# STM8_DevBoard.net
KiCad netlist of a schematic drawn in Altium Designer
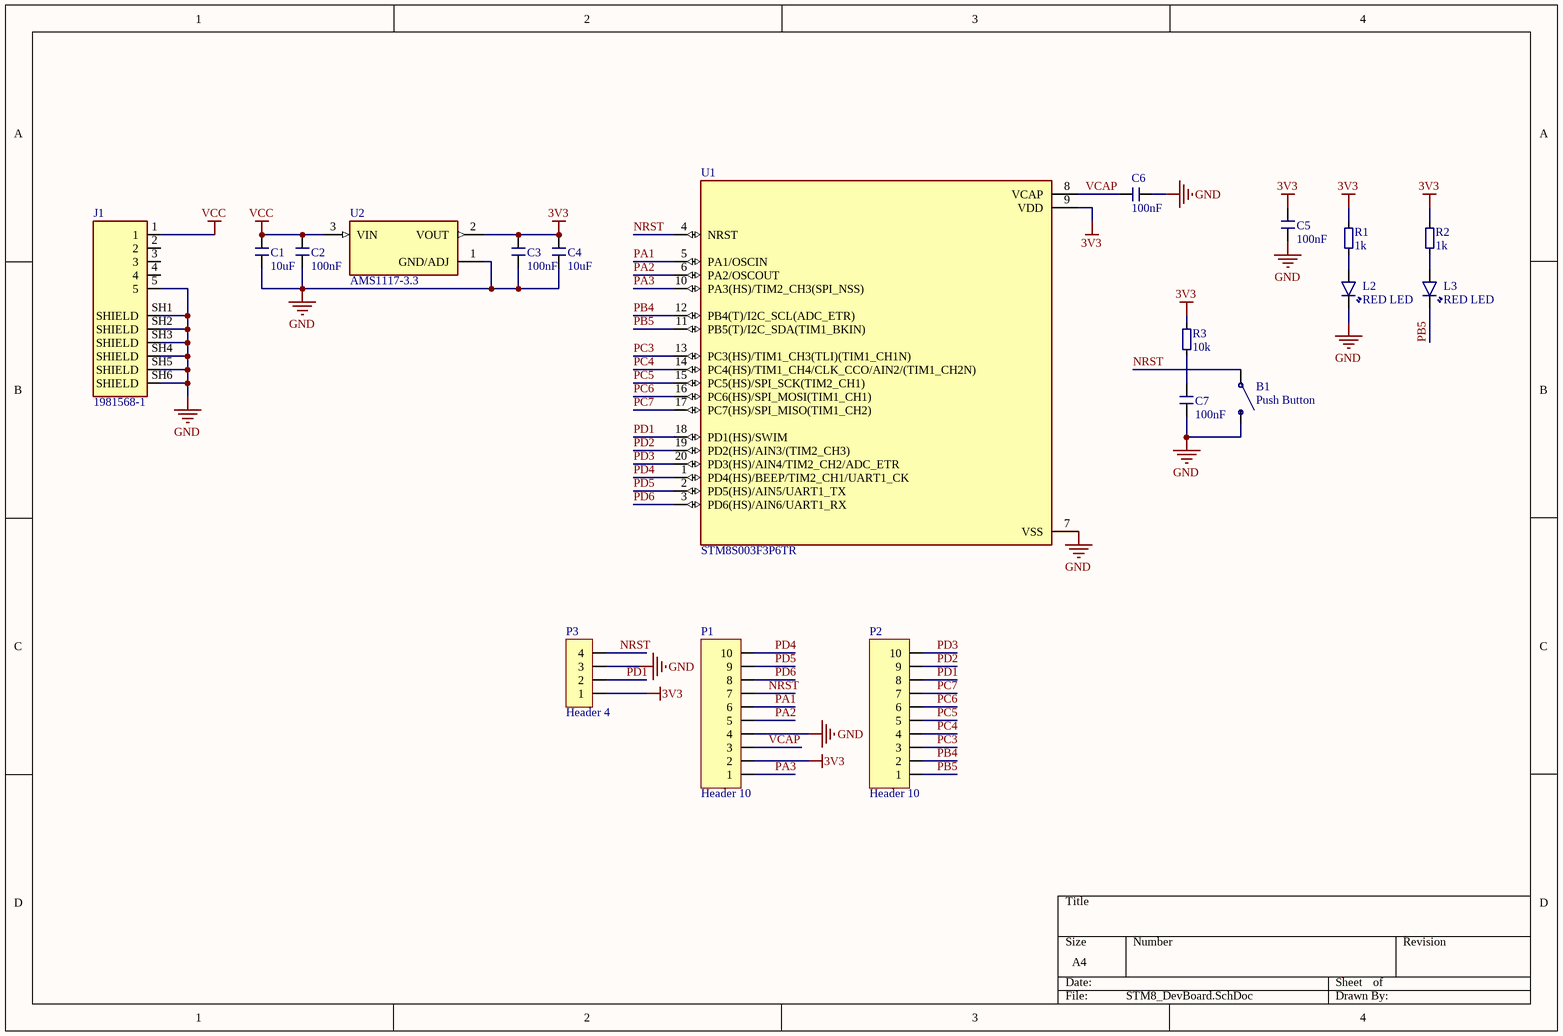
[diagram p0: STM8_DevBoard.SchDoc]

(export (version "E")
  (design (tool "Eeschema 10.0.6"))
  (components
    (comp (ref "B1")
      (value "Push Button")
      (footprint "NRST")
      (libsource (lib "STM8_DevBoard") (part "Push Button"))
    )
    (comp (ref "C1")
      (value "10uF")
      (footprint "1206_Capacitor")
      (libsource (lib "STM8_DevBoard") (part "1206_Capacitor"))
    )
    (comp (ref "C2")
      (value "100nF")
      (footprint "1206_Capacitor")
      (libsource (lib "STM8_DevBoard") (part "1206_Capacitor"))
    )
    (comp (ref "C3")
      (value "100nF")
      (footprint "1206_Capacitor")
      (libsource (lib "STM8_DevBoard") (part "1206_Capacitor"))
    )
    (comp (ref "C4")
      (value "10uF")
      (footprint "1206_Capacitor")
      (libsource (lib "STM8_DevBoard") (part "1206_Capacitor"))
    )
    (comp (ref "C5")
      (value "100nF")
      (footprint "1206_Capacitor")
      (libsource (lib "STM8_DevBoard") (part "1206_Capacitor"))
    )
    (comp (ref "C6")
      (value "100nF")
      (footprint "1206_Capacitor")
      (libsource (lib "STM8_DevBoard") (part "1206_Capacitor"))
    )
    (comp (ref "C7")
      (value "100nF")
      (footprint "1206_Capacitor")
      (libsource (lib "STM8_DevBoard") (part "1206_Capacitor"))
    )
    (comp (ref "J1")
      (value "1981568-1")
      (footprint "TE_1981568-1")
      (libsource (lib "1981568-1") (part "1981568-1"))
    )
    (comp (ref "L2")
      (value "RED LED")
      (footprint "0805_LED")
      (libsource (lib "STM8_DevBoard") (part "0805_LED"))
    )
    (comp (ref "L3")
      (value "RED LED")
      (footprint "0805_LED")
      (libsource (lib "STM8_DevBoard") (part "0805_LED"))
    )
    (comp (ref "P1")
      (value "Header 10")
      (footprint "Header 10")
      (libsource (lib "STM8_DevBoard") (part "Header 10"))
    )
    (comp (ref "P2")
      (value "Header 10")
      (footprint "Header 10")
      (libsource (lib "STM8_DevBoard") (part "Header 10"))
    )
    (comp (ref "P3")
      (value "Header 4")
      (footprint "Header 4")
      (libsource (lib "STM8_DevBoard") (part "Header 4"))
    )
    (comp (ref "R1")
      (value "1k")
      (footprint "1206 Resistor")
      (libsource (lib "STM8_DevBoard") (part "1206 Resistor"))
    )
    (comp (ref "R2")
      (value "1k")
      (footprint "1206 Resistor")
      (libsource (lib "STM8_DevBoard") (part "1206 Resistor"))
    )
    (comp (ref "R3")
      (value "10k")
      (footprint "1206 Resistor")
      (libsource (lib "STM8_DevBoard") (part "1206 Resistor"))
    )
    (comp (ref "U1")
      (value "STM8S003F3P6TR")
      (footprint "SOP65P640X120-20N")
      (description "STM8 STM8S Microcontroller IC 8-Bit 16MHz 8KB (8K x 8) FLASH 20-TSSOP")
      (fields (field (name "MF") "STMicroelectronics"))
      (libsource (lib "STM8S003F3P6TR") (part "STM8S003F3P6TR"))
    )
    (comp (ref "U2")
      (value "AMS1117-3.3")
      (footprint "SOT229P700X180-4N")
      (description "Sot223/Pkg 1-Amp 3.3-Volt Low Drop Out Voltage Regulatator")
      (fields (field (name "MF") "Advanced Monolithic Systems"))
      (libsource (lib "AMS1117-3.3") (part "AMS1117-3.3"))
    )
  )
  (nets
    (net (code "1") (name "/NRST") (class "Default")
      (node (ref "B1") (pin "1") (pinfunction "1_1") (pintype "passive"))
      (node (ref "P1") (pin "7") (pinfunction "7_7") (pintype "passive"))
      (node (ref "P3") (pin "4") (pinfunction "4_4") (pintype "passive"))
      (node (ref "U1") (pin "4") (pinfunction "NRST_4") (pintype "bidirectional"))
    )
    (net (code "2") (name "/PA1") (class "Default")
      (node (ref "P1") (pin "6") (pinfunction "6_6") (pintype "passive"))
      (node (ref "U1") (pin "5") (pinfunction "PA1/OSCIN_5") (pintype "bidirectional"))
    )
    (net (code "3") (name "/PA2") (class "Default")
      (node (ref "P1") (pin "5") (pinfunction "5_5") (pintype "passive"))
      (node (ref "U1") (pin "6") (pinfunction "PA2/OSCOUT_6") (pintype "bidirectional"))
    )
    (net (code "4") (name "/PA3") (class "Default")
      (node (ref "P1") (pin "1") (pinfunction "1_1") (pintype "passive"))
      (node (ref "U1") (pin "10") (pinfunction "PA3(HS)/TIM2_CH3(SPI_NSS)_10") (pintype "bidirectional"))
    )
    (net (code "5") (name "/PB4") (class "Default")
      (node (ref "P2") (pin "2") (pinfunction "2_2") (pintype "passive"))
      (node (ref "U1") (pin "12") (pinfunction "PB4(T)/I2C_SCL(ADC_ETR)_12") (pintype "bidirectional"))
    )
    (net (code "6") (name "/PB5") (class "Default")
      (node (ref "L3") (pin "L_2") (pinfunction "L_2_L_2") (pintype "passive"))
      (node (ref "P2") (pin "1") (pinfunction "1_1") (pintype "passive"))
      (node (ref "U1") (pin "11") (pinfunction "PB5(T)/I2C_SDA(TIM1_BKIN)_11") (pintype "bidirectional"))
    )
    (net (code "7") (name "/PC3") (class "Default")
      (node (ref "P2") (pin "3") (pinfunction "3_3") (pintype "passive"))
      (node (ref "U1") (pin "13") (pinfunction "PC3(HS)/TIM1_CH3(TLI)(TIM1_CH1N)_13") (pintype "bidirectional"))
    )
    (net (code "8") (name "/PC4") (class "Default")
      (node (ref "P2") (pin "4") (pinfunction "4_4") (pintype "passive"))
      (node (ref "U1") (pin "14") (pinfunction "PC4(HS)/TIM1_CH4/CLK_CCO/AIN2/(TIM1_CH2N)_14") (pintype "bidirectional"))
    )
    (net (code "9") (name "/PC5") (class "Default")
      (node (ref "P2") (pin "5") (pinfunction "5_5") (pintype "passive"))
      (node (ref "U1") (pin "15") (pinfunction "PC5(HS)/SPI_SCK(TIM2_CH1)_15") (pintype "bidirectional"))
    )
    (net (code "10") (name "/PC6") (class "Default")
      (node (ref "P2") (pin "6") (pinfunction "6_6") (pintype "passive"))
      (node (ref "U1") (pin "16") (pinfunction "PC6(HS)/SPI_MOSI(TIM1_CH1)_16") (pintype "bidirectional"))
    )
    (net (code "11") (name "/PC7") (class "Default")
      (node (ref "P2") (pin "7") (pinfunction "7_7") (pintype "passive"))
      (node (ref "U1") (pin "17") (pinfunction "PC7(HS)/SPI_MISO(TIM1_CH2)_17") (pintype "bidirectional"))
    )
    (net (code "12") (name "/PD1") (class "Default")
      (node (ref "P2") (pin "8") (pinfunction "8_8") (pintype "passive"))
      (node (ref "P3") (pin "2") (pinfunction "2_2") (pintype "passive"))
      (node (ref "U1") (pin "18") (pinfunction "PD1(HS)/SWIM_18") (pintype "bidirectional"))
    )
    (net (code "13") (name "/PD2") (class "Default")
      (node (ref "P2") (pin "9") (pinfunction "9_9") (pintype "passive"))
      (node (ref "U1") (pin "19") (pinfunction "PD2(HS)/AIN3/(TIM2_CH3)_19") (pintype "bidirectional"))
    )
    (net (code "14") (name "/PD3") (class "Default")
      (node (ref "P2") (pin "10") (pinfunction "10_10") (pintype "passive"))
      (node (ref "U1") (pin "20") (pinfunction "PD3(HS)/AIN4/TIM2_CH2/ADC_ETR_20") (pintype "bidirectional"))
    )
    (net (code "15") (name "/PD4") (class "Default")
      (node (ref "P1") (pin "10") (pinfunction "10_10") (pintype "passive"))
      (node (ref "U1") (pin "1") (pinfunction "PD4(HS)/BEEP/TIM2_CH1/UART1_CK_1") (pintype "bidirectional"))
    )
    (net (code "16") (name "/PD5") (class "Default")
      (node (ref "P1") (pin "9") (pinfunction "9_9") (pintype "passive"))
      (node (ref "U1") (pin "2") (pinfunction "PD5(HS)/AIN5/UART1_TX_2") (pintype "bidirectional"))
    )
    (net (code "17") (name "/PD6") (class "Default")
      (node (ref "P1") (pin "8") (pinfunction "8_8") (pintype "passive"))
      (node (ref "U1") (pin "3") (pinfunction "PD6(HS)/AIN6/UART1_RX_3") (pintype "bidirectional"))
    )
    (net (code "18") (name "/VCAP") (class "Default")
      (node (ref "C6") (pin "1") (pinfunction "1_1") (pintype "passive"))
      (node (ref "P1") (pin "3") (pinfunction "3_3") (pintype "passive"))
      (node (ref "U1") (pin "8") (pinfunction "VCAP_8") (pintype "power_in"))
    )
    (net (code "19") (name "3V3") (class "Default")
      (node (ref "C3") (pin "2") (pinfunction "2_2") (pintype "passive"))
      (node (ref "C4") (pin "1") (pinfunction "1_1") (pintype "passive"))
      (node (ref "C5") (pin "2") (pinfunction "2_2") (pintype "passive"))
      (node (ref "P1") (pin "2") (pinfunction "2_2") (pintype "passive"))
      (node (ref "P3") (pin "1") (pinfunction "1_1") (pintype "passive"))
      (node (ref "R1") (pin "2") (pinfunction "2_2") (pintype "passive"))
      (node (ref "R2") (pin "2") (pinfunction "2_2") (pintype "passive"))
      (node (ref "R3") (pin "2") (pinfunction "2_2") (pintype "passive"))
      (node (ref "U1") (pin "9") (pinfunction "VDD_9") (pintype "power_in"))
      (node (ref "U2") (pin "2") (pinfunction "VOUT_2") (pintype "output"))
    )
    (net (code "20") (name "GND") (class "Default")
      (node (ref "B1") (pin "2") (pinfunction "2_2") (pintype "passive"))
      (node (ref "C1") (pin "1") (pinfunction "1_1") (pintype "passive"))
      (node (ref "C2") (pin "1") (pinfunction "1_1") (pintype "passive"))
      (node (ref "C3") (pin "1") (pinfunction "1_1") (pintype "passive"))
      (node (ref "C4") (pin "2") (pinfunction "2_2") (pintype "passive"))
      (node (ref "C5") (pin "1") (pinfunction "1_1") (pintype "passive"))
      (node (ref "C6") (pin "2") (pinfunction "2_2") (pintype "passive"))
      (node (ref "C7") (pin "1") (pinfunction "1_1") (pintype "passive"))
      (node (ref "J1") (pin "5") (pinfunction "5_5") (pintype "passive"))
      (node (ref "J1") (pin "SH1") (pinfunction "SHIELD_SH1") (pintype "passive"))
      (node (ref "J1") (pin "SH2") (pinfunction "SHIELD_SH2") (pintype "passive"))
      (node (ref "J1") (pin "SH3") (pinfunction "SHIELD_SH3") (pintype "passive"))
      (node (ref "J1") (pin "SH4") (pinfunction "SHIELD_SH4") (pintype "passive"))
      (node (ref "J1") (pin "SH5") (pinfunction "SHIELD_SH5") (pintype "passive"))
      (node (ref "J1") (pin "SH6") (pinfunction "SHIELD_SH6") (pintype "passive"))
      (node (ref "L2") (pin "L_2") (pinfunction "L_2_L_2") (pintype "passive"))
      (node (ref "P1") (pin "4") (pinfunction "4_4") (pintype "passive"))
      (node (ref "P3") (pin "3") (pinfunction "3_3") (pintype "passive"))
      (node (ref "U1") (pin "7") (pinfunction "VSS_7") (pintype "power_in"))
      (node (ref "U2") (pin "1") (pinfunction "GND/ADJ_1") (pintype "power_in"))
    )
    (net (code "21") (name "Net-(C7-Pad2)") (class "Default")
      (node (ref "C7") (pin "2") (pinfunction "2_2") (pintype "passive"))
      (node (ref "R3") (pin "1") (pinfunction "1_1") (pintype "passive"))
    )
    (net (code "22") (name "Net-(L2-PadL_1)") (class "Default")
      (node (ref "L2") (pin "L_1") (pinfunction "L_1_L_1") (pintype "passive"))
      (node (ref "R1") (pin "1") (pinfunction "1_1") (pintype "passive"))
    )
    (net (code "23") (name "Net-(L3-PadL_1)") (class "Default")
      (node (ref "L3") (pin "L_1") (pinfunction "L_1_L_1") (pintype "passive"))
      (node (ref "R2") (pin "1") (pinfunction "1_1") (pintype "passive"))
    )
    (net (code "24") (name "VCC") (class "Default")
      (node (ref "C1") (pin "2") (pinfunction "2_2") (pintype "passive"))
      (node (ref "C2") (pin "2") (pinfunction "2_2") (pintype "passive"))
      (node (ref "J1") (pin "1") (pinfunction "1_1") (pintype "passive"))
      (node (ref "U2") (pin "3") (pinfunction "VIN_3") (pintype "input"))
    )
    (net (code "25") (name "unconnected-(J1-Pad2)") (class "Default")
      (node (ref "J1") (pin "2") (pinfunction "2_2") (pintype "passive"))
    )
    (net (code "26") (name "unconnected-(J1-Pad3)") (class "Default")
      (node (ref "J1") (pin "3") (pinfunction "3_3") (pintype "passive"))
    )
    (net (code "27") (name "unconnected-(J1-Pad4)") (class "Default")
      (node (ref "J1") (pin "4") (pinfunction "4_4") (pintype "passive"))
    )
  )
)
